# InterfacesB_FPGA.net
KiCad netlist of a schematic drawn in Altium Designer
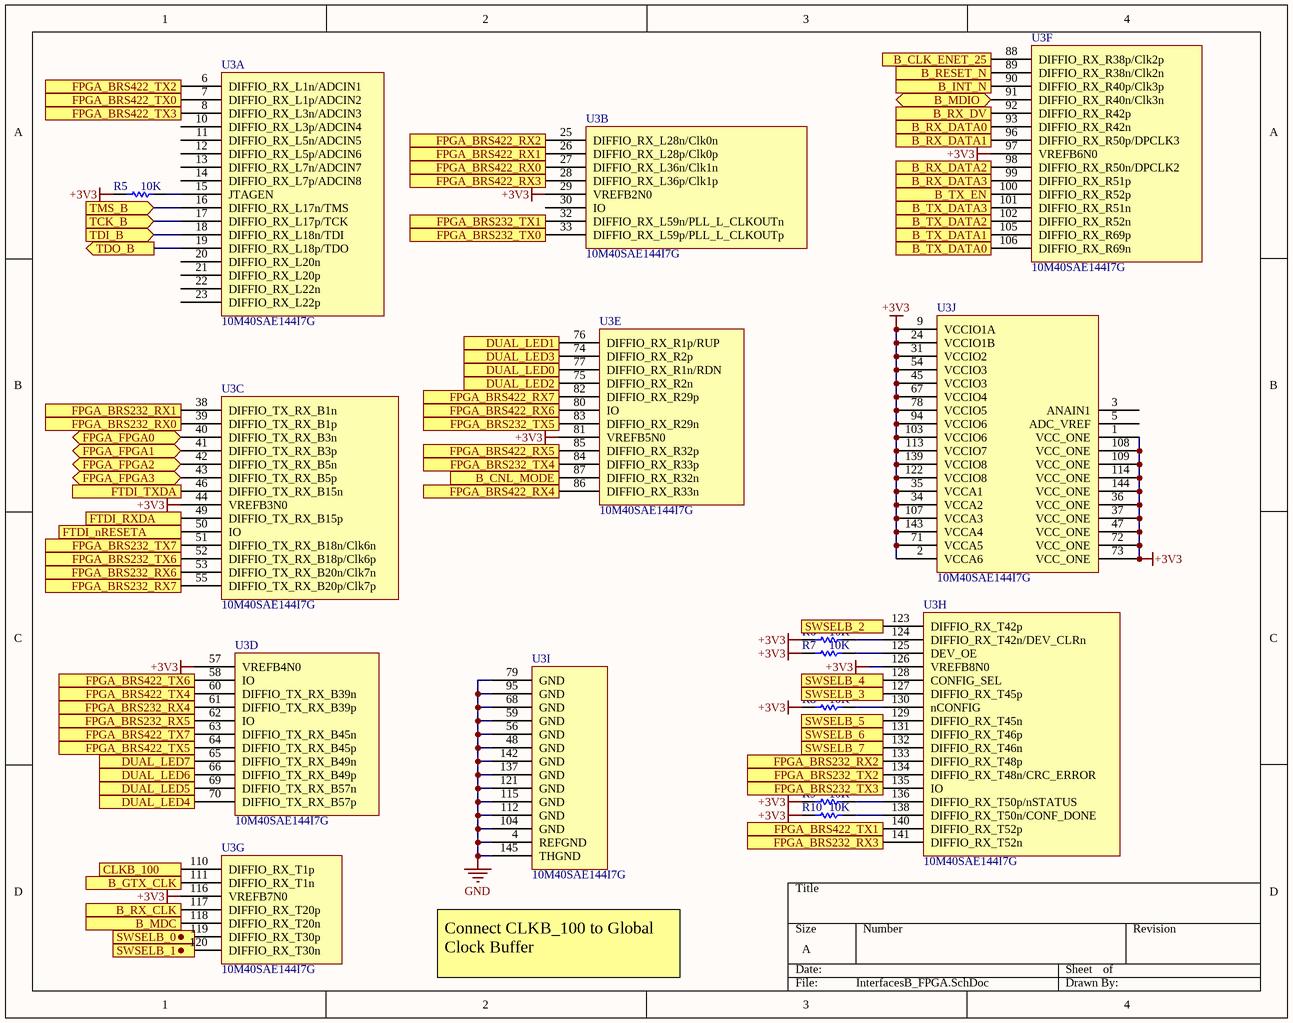
[diagram p0: InterfacesB_FPGA.SchDoc]

(export (version "E")
  (design (tool "Eeschema 10.0.6"))
  (components
    (comp (ref "R5")
      (value "10K")
      (footprint "RES_0805")
      (fields (field (name "Comment") "RES_0805"))
      (libsource (lib "AdapterLib") (part "RES_0805"))
    )
    (comp (ref "R6")
      (value "10K")
      (footprint "RES_0805")
      (fields (field (name "Comment") "RES_0805"))
      (libsource (lib "AdapterLib") (part "RES_0805"))
    )
    (comp (ref "R7")
      (value "10K")
      (footprint "RES_0805")
      (fields (field (name "Comment") "RES_0805"))
      (libsource (lib "AdapterLib") (part "RES_0805"))
    )
    (comp (ref "R8")
      (value "10K")
      (footprint "RES_0805")
      (fields (field (name "Comment") "RES_0805"))
      (libsource (lib "AdapterLib") (part "RES_0805"))
    )
    (comp (ref "R9")
      (value "10K")
      (footprint "RES_0805")
      (fields (field (name "Comment") "RES_0805"))
      (libsource (lib "AdapterLib") (part "RES_0805"))
    )
    (comp (ref "R10")
      (value "10K")
      (footprint "RES_0805")
      (fields (field (name "Comment") "RES_0805"))
      (libsource (lib "AdapterLib") (part "RES_0805"))
    )
    (comp (ref "U3")
      (value "10M40SAE144I7G")
      (footprint "10M40SAE144I7G")
      (description "IC FPGA 101 I/O 144EQFP")
      (libsource (lib "AdapterLib") (part "10M40SAE144I7G"))
    )
  )
  (nets
    (net (code "1") (name "+3V3") (class "Default")
      (node (ref "R10") (pin "2") (pinfunction "2_2") (pintype "passive"))
      (node (ref "R5") (pin "2") (pinfunction "2_2") (pintype "passive"))
      (node (ref "R6") (pin "2") (pinfunction "2_2") (pintype "passive"))
      (node (ref "R7") (pin "2") (pinfunction "2_2") (pintype "passive"))
      (node (ref "R8") (pin "2") (pinfunction "2_2") (pintype "passive"))
      (node (ref "R9") (pin "2") (pinfunction "2_2") (pintype "passive"))
      (node (ref "U3") (pin "1") (pinfunction "VCC_ONE_1") (pintype "passive"))
      (node (ref "U3") (pin "103") (pinfunction "VCCIO6_103") (pintype "passive"))
      (node (ref "U3") (pin "107") (pinfunction "VCCA3_107") (pintype "passive"))
      (node (ref "U3") (pin "108") (pinfunction "VCC_ONE_108") (pintype "passive"))
      (node (ref "U3") (pin "109") (pinfunction "VCC_ONE_109") (pintype "passive"))
      (node (ref "U3") (pin "113") (pinfunction "VCCIO7_113") (pintype "passive"))
      (node (ref "U3") (pin "114") (pinfunction "VCC_ONE_114") (pintype "passive"))
      (node (ref "U3") (pin "116") (pinfunction "VREFB7N0_116") (pintype "passive"))
      (node (ref "U3") (pin "122") (pinfunction "VCCIO8_122") (pintype "passive"))
      (node (ref "U3") (pin "126") (pinfunction "VREFB8N0_126") (pintype "passive"))
      (node (ref "U3") (pin "139") (pinfunction "VCCIO8_139") (pintype "passive"))
      (node (ref "U3") (pin "143") (pinfunction "VCCA4_143") (pintype "passive"))
      (node (ref "U3") (pin "144") (pinfunction "VCC_ONE_144") (pintype "passive"))
      (node (ref "U3") (pin "2") (pinfunction "VCCA6_2") (pintype "passive"))
      (node (ref "U3") (pin "24") (pinfunction "VCCIO1B_24") (pintype "passive"))
      (node (ref "U3") (pin "29") (pinfunction "VREFB2N0_29") (pintype "passive"))
      (node (ref "U3") (pin "31") (pinfunction "VCCIO2_31") (pintype "passive"))
      (node (ref "U3") (pin "34") (pinfunction "VCCA2_34") (pintype "passive"))
      (node (ref "U3") (pin "35") (pinfunction "VCCA1_35") (pintype "passive"))
      (node (ref "U3") (pin "36") (pinfunction "VCC_ONE_36") (pintype "passive"))
      (node (ref "U3") (pin "37") (pinfunction "VCC_ONE_37") (pintype "passive"))
      (node (ref "U3") (pin "44") (pinfunction "VREFB3N0_44") (pintype "passive"))
      (node (ref "U3") (pin "45") (pinfunction "VCCIO3_45") (pintype "passive"))
      (node (ref "U3") (pin "47") (pinfunction "VCC_ONE_47") (pintype "passive"))
      (node (ref "U3") (pin "54") (pinfunction "VCCIO3_54") (pintype "passive"))
      (node (ref "U3") (pin "57") (pinfunction "VREFB4N0_57") (pintype "passive"))
      (node (ref "U3") (pin "67") (pinfunction "VCCIO4_67") (pintype "passive"))
      (node (ref "U3") (pin "71") (pinfunction "VCCA5_71") (pintype "passive"))
      (node (ref "U3") (pin "72") (pinfunction "VCC_ONE_72") (pintype "passive"))
      (node (ref "U3") (pin "73") (pinfunction "VCC_ONE_73") (pintype "passive"))
      (node (ref "U3") (pin "78") (pinfunction "VCCIO5_78") (pintype "passive"))
      (node (ref "U3") (pin "81") (pinfunction "VREFB5N0_81") (pintype "passive"))
      (node (ref "U3") (pin "9") (pinfunction "VCCIO1A_9") (pintype "passive"))
      (node (ref "U3") (pin "94") (pinfunction "VCCIO6_94") (pintype "passive"))
      (node (ref "U3") (pin "97") (pinfunction "VREFB6N0_97") (pintype "passive"))
    )
    (net (code "2") (name "/B_CLK_ENET_25") (class "Default")
      (node (ref "U3") (pin "88") (pinfunction "DIFFIO_RX_R38p/Clk2p_88") (pintype "passive"))
    )
    (net (code "3") (name "/B_CNL_MODE") (class "Default")
      (node (ref "U3") (pin "87") (pinfunction "DIFFIO_RX_R32n_87") (pintype "passive"))
    )
    (net (code "4") (name "/B_GTX_CLK") (class "Default")
      (node (ref "U3") (pin "111") (pinfunction "DIFFIO_RX_T1n_111") (pintype "passive"))
    )
    (net (code "5") (name "/B_INT_N") (class "Default")
      (node (ref "U3") (pin "90") (pinfunction "DIFFIO_RX_R40p/Clk3p_90") (pintype "passive"))
    )
    (net (code "6") (name "/B_MDC") (class "Default")
      (node (ref "U3") (pin "118") (pinfunction "DIFFIO_RX_T20n_118") (pintype "passive"))
    )
    (net (code "7") (name "/B_MDIO") (class "Default")
      (node (ref "U3") (pin "91") (pinfunction "DIFFIO_RX_R40n/Clk3n_91") (pintype "passive"))
    )
    (net (code "8") (name "/B_RESET_N") (class "Default")
      (node (ref "U3") (pin "89") (pinfunction "DIFFIO_RX_R38n/Clk2n_89") (pintype "passive"))
    )
    (net (code "9") (name "/B_RX_CLK") (class "Default")
      (node (ref "U3") (pin "117") (pinfunction "DIFFIO_RX_T20p_117") (pintype "passive"))
    )
    (net (code "10") (name "/B_RX_DATA0") (class "Default")
      (node (ref "U3") (pin "93") (pinfunction "DIFFIO_RX_R42n_93") (pintype "passive"))
    )
    (net (code "11") (name "/B_RX_DATA1") (class "Default")
      (node (ref "U3") (pin "96") (pinfunction "DIFFIO_RX_R50p/DPCLK3_96") (pintype "passive"))
    )
    (net (code "12") (name "/B_RX_DATA2") (class "Default")
      (node (ref "U3") (pin "98") (pinfunction "DIFFIO_RX_R50n/DPCLK2_98") (pintype "passive"))
    )
    (net (code "13") (name "/B_RX_DATA3") (class "Default")
      (node (ref "U3") (pin "99") (pinfunction "DIFFIO_RX_R51p_99") (pintype "passive"))
    )
    (net (code "14") (name "/B_RX_DV") (class "Default")
      (node (ref "U3") (pin "92") (pinfunction "DIFFIO_RX_R42p_92") (pintype "passive"))
    )
    (net (code "15") (name "/B_TX_DATA0") (class "Default")
      (node (ref "U3") (pin "106") (pinfunction "DIFFIO_RX_R69n_106") (pintype "passive"))
    )
    (net (code "16") (name "/B_TX_DATA1") (class "Default")
      (node (ref "U3") (pin "105") (pinfunction "DIFFIO_RX_R69p_105") (pintype "passive"))
    )
    (net (code "17") (name "/B_TX_DATA2") (class "Default")
      (node (ref "U3") (pin "102") (pinfunction "DIFFIO_RX_R52n_102") (pintype "passive"))
    )
    (net (code "18") (name "/B_TX_DATA3") (class "Default")
      (node (ref "U3") (pin "101") (pinfunction "DIFFIO_RX_R51n_101") (pintype "passive"))
    )
    (net (code "19") (name "/B_TX_EN") (class "Default")
      (node (ref "U3") (pin "100") (pinfunction "DIFFIO_RX_R52p_100") (pintype "passive"))
    )
    (net (code "20") (name "/CLKB_100") (class "Default")
      (node (ref "U3") (pin "110") (pinfunction "DIFFIO_RX_T1p_110") (pintype "passive"))
    )
    (net (code "21") (name "/DUAL_LED0") (class "Default")
      (node (ref "U3") (pin "77") (pinfunction "DIFFIO_RX_R1n/RDN_77") (pintype "passive"))
    )
    (net (code "22") (name "/DUAL_LED1") (class "Default")
      (node (ref "U3") (pin "76") (pinfunction "DIFFIO_RX_R1p/RUP_76") (pintype "passive"))
    )
    (net (code "23") (name "/DUAL_LED2") (class "Default")
      (node (ref "U3") (pin "75") (pinfunction "DIFFIO_RX_R2n_75") (pintype "passive"))
    )
    (net (code "24") (name "/DUAL_LED3") (class "Default")
      (node (ref "U3") (pin "74") (pinfunction "DIFFIO_RX_R2p_74") (pintype "passive"))
    )
    (net (code "25") (name "/DUAL_LED4") (class "Default")
      (node (ref "U3") (pin "70") (pinfunction "DIFFIO_TX_RX_B57p_70") (pintype "passive"))
    )
    (net (code "26") (name "/DUAL_LED5") (class "Default")
      (node (ref "U3") (pin "69") (pinfunction "DIFFIO_TX_RX_B57n_69") (pintype "passive"))
    )
    (net (code "27") (name "/DUAL_LED6") (class "Default")
      (node (ref "U3") (pin "66") (pinfunction "DIFFIO_TX_RX_B49p_66") (pintype "passive"))
    )
    (net (code "28") (name "/DUAL_LED7") (class "Default")
      (node (ref "U3") (pin "65") (pinfunction "DIFFIO_TX_RX_B49n_65") (pintype "passive"))
    )
    (net (code "29") (name "/FPGA_BRS232_RX0") (class "Default")
      (node (ref "U3") (pin "39") (pinfunction "DIFFIO_TX_RX_B1p_39") (pintype "passive"))
    )
    (net (code "30") (name "/FPGA_BRS232_RX1") (class "Default")
      (node (ref "U3") (pin "38") (pinfunction "DIFFIO_TX_RX_B1n_38") (pintype "passive"))
    )
    (net (code "31") (name "/FPGA_BRS232_RX2") (class "Default")
      (node (ref "U3") (pin "133") (pinfunction "DIFFIO_RX_T48p_133") (pintype "passive"))
    )
    (net (code "32") (name "/FPGA_BRS232_RX3") (class "Default")
      (node (ref "U3") (pin "141") (pinfunction "DIFFIO_RX_T52n_141") (pintype "passive"))
    )
    (net (code "33") (name "/FPGA_BRS232_RX4") (class "Default")
      (node (ref "U3") (pin "61") (pinfunction "DIFFIO_TX_RX_B39p_61") (pintype "passive"))
    )
    (net (code "34") (name "/FPGA_BRS232_RX5") (class "Default")
      (node (ref "U3") (pin "62") (pinfunction "IO_62") (pintype "passive"))
    )
    (net (code "35") (name "/FPGA_BRS232_RX6") (class "Default")
      (node (ref "U3") (pin "53") (pinfunction "DIFFIO_TX_RX_B20n/Clk7n_53") (pintype "passive"))
    )
    (net (code "36") (name "/FPGA_BRS232_RX7") (class "Default")
      (node (ref "U3") (pin "55") (pinfunction "DIFFIO_TX_RX_B20p/Clk7p_55") (pintype "passive"))
    )
    (net (code "37") (name "/FPGA_BRS232_TX0") (class "Default")
      (node (ref "U3") (pin "33") (pinfunction "DIFFIO_RX_L59p/PLL_L_CLKOUTp_33") (pintype "passive"))
    )
    (net (code "38") (name "/FPGA_BRS232_TX1") (class "Default")
      (node (ref "U3") (pin "32") (pinfunction "DIFFIO_RX_L59n/PLL_L_CLKOUTn_32") (pintype "passive"))
    )
    (net (code "39") (name "/FPGA_BRS232_TX2") (class "Default")
      (node (ref "U3") (pin "134") (pinfunction "DIFFIO_RX_T48n/CRC_ERROR_134") (pintype "passive"))
    )
    (net (code "40") (name "/FPGA_BRS232_TX3") (class "Default")
      (node (ref "U3") (pin "135") (pinfunction "IO_135") (pintype "passive"))
    )
    (net (code "41") (name "/FPGA_BRS232_TX4") (class "Default")
      (node (ref "U3") (pin "84") (pinfunction "DIFFIO_RX_R33p_84") (pintype "passive"))
    )
    (net (code "42") (name "/FPGA_BRS232_TX5") (class "Default")
      (node (ref "U3") (pin "83") (pinfunction "DIFFIO_RX_R29n_83") (pintype "passive"))
    )
    (net (code "43") (name "/FPGA_BRS232_TX6") (class "Default")
      (node (ref "U3") (pin "52") (pinfunction "DIFFIO_TX_RX_B18p/Clk6p_52") (pintype "passive"))
    )
    (net (code "44") (name "/FPGA_BRS232_TX7") (class "Default")
      (node (ref "U3") (pin "51") (pinfunction "DIFFIO_TX_RX_B18n/Clk6n_51") (pintype "passive"))
    )
    (net (code "45") (name "/FPGA_BRS422_RX0") (class "Default")
      (node (ref "U3") (pin "27") (pinfunction "DIFFIO_RX_L36n/Clk1n_27") (pintype "passive"))
    )
    (net (code "46") (name "/FPGA_BRS422_RX1") (class "Default")
      (node (ref "U3") (pin "26") (pinfunction "DIFFIO_RX_L28p/Clk0p_26") (pintype "passive"))
    )
    (net (code "47") (name "/FPGA_BRS422_RX2") (class "Default")
      (node (ref "U3") (pin "25") (pinfunction "DIFFIO_RX_L28n/Clk0n_25") (pintype "passive"))
    )
    (net (code "48") (name "/FPGA_BRS422_RX3") (class "Default")
      (node (ref "U3") (pin "28") (pinfunction "DIFFIO_RX_L36p/Clk1p_28") (pintype "passive"))
    )
    (net (code "49") (name "/FPGA_BRS422_RX4") (class "Default")
      (node (ref "U3") (pin "86") (pinfunction "DIFFIO_RX_R33n_86") (pintype "passive"))
    )
    (net (code "50") (name "/FPGA_BRS422_RX5") (class "Default")
      (node (ref "U3") (pin "85") (pinfunction "DIFFIO_RX_R32p_85") (pintype "passive"))
    )
    (net (code "51") (name "/FPGA_BRS422_RX6") (class "Default")
      (node (ref "U3") (pin "80") (pinfunction "IO_80") (pintype "passive"))
    )
    (net (code "52") (name "/FPGA_BRS422_RX7") (class "Default")
      (node (ref "U3") (pin "82") (pinfunction "DIFFIO_RX_R29p_82") (pintype "passive"))
    )
    (net (code "53") (name "/FPGA_BRS422_TX0") (class "Default")
      (node (ref "U3") (pin "7") (pinfunction "DIFFIO_RX_L1p/ADCIN2_7") (pintype "passive"))
    )
    (net (code "54") (name "/FPGA_BRS422_TX1") (class "Default")
      (node (ref "U3") (pin "140") (pinfunction "DIFFIO_RX_T52p_140") (pintype "passive"))
    )
    (net (code "55") (name "/FPGA_BRS422_TX2") (class "Default")
      (node (ref "U3") (pin "6") (pinfunction "DIFFIO_RX_L1n/ADCIN1_6") (pintype "passive"))
    )
    (net (code "56") (name "/FPGA_BRS422_TX3") (class "Default")
      (node (ref "U3") (pin "8") (pinfunction "DIFFIO_RX_L3n/ADCIN3_8") (pintype "passive"))
    )
    (net (code "57") (name "/FPGA_BRS422_TX4") (class "Default")
      (node (ref "U3") (pin "60") (pinfunction "DIFFIO_TX_RX_B39n_60") (pintype "passive"))
    )
    (net (code "58") (name "/FPGA_BRS422_TX5") (class "Default")
      (node (ref "U3") (pin "64") (pinfunction "DIFFIO_TX_RX_B45p_64") (pintype "passive"))
    )
    (net (code "59") (name "/FPGA_BRS422_TX6") (class "Default")
      (node (ref "U3") (pin "58") (pinfunction "IO_58") (pintype "passive"))
    )
    (net (code "60") (name "/FPGA_BRS422_TX7") (class "Default")
      (node (ref "U3") (pin "63") (pinfunction "DIFFIO_TX_RX_B45n_63") (pintype "passive"))
    )
    (net (code "61") (name "/FPGA_FPGA0") (class "Default")
      (node (ref "U3") (pin "40") (pinfunction "DIFFIO_TX_RX_B3n_40") (pintype "passive"))
    )
    (net (code "62") (name "/FPGA_FPGA1") (class "Default")
      (node (ref "U3") (pin "41") (pinfunction "DIFFIO_TX_RX_B3p_41") (pintype "passive"))
    )
    (net (code "63") (name "/FPGA_FPGA2") (class "Default")
      (node (ref "U3") (pin "42") (pinfunction "DIFFIO_TX_RX_B5n_42") (pintype "passive"))
    )
    (net (code "64") (name "/FPGA_FPGA3") (class "Default")
      (node (ref "U3") (pin "43") (pinfunction "DIFFIO_TX_RX_B5p_43") (pintype "passive"))
    )
    (net (code "65") (name "/FTDI_RXDA") (class "Default")
      (node (ref "U3") (pin "49") (pinfunction "DIFFIO_TX_RX_B15p_49") (pintype "passive"))
    )
    (net (code "66") (name "/FTDI_TXDA") (class "Default")
      (node (ref "U3") (pin "46") (pinfunction "DIFFIO_TX_RX_B15n_46") (pintype "passive"))
    )
    (net (code "67") (name "/FTDI_nRESETA") (class "Default")
      (node (ref "U3") (pin "50") (pinfunction "IO_50") (pintype "passive"))
    )
    (net (code "70") (name "/SWSELB_2") (class "Default")
      (node (ref "U3") (pin "123") (pinfunction "DIFFIO_RX_T42p_123") (pintype "passive"))
    )
    (net (code "71") (name "/SWSELB_3") (class "Default")
      (node (ref "U3") (pin "127") (pinfunction "DIFFIO_RX_T45p_127") (pintype "passive"))
    )
    (net (code "72") (name "/SWSELB_4") (class "Default")
      (node (ref "U3") (pin "128") (pinfunction "CONFIG_SEL_128") (pintype "passive"))
    )
    (net (code "73") (name "/SWSELB_5") (class "Default")
      (node (ref "U3") (pin "129") (pinfunction "DIFFIO_RX_T45n_129") (pintype "passive"))
    )
    (net (code "74") (name "/SWSELB_6") (class "Default")
      (node (ref "U3") (pin "131") (pinfunction "DIFFIO_RX_T46p_131") (pintype "passive"))
    )
    (net (code "75") (name "/SWSELB_7") (class "Default")
      (node (ref "U3") (pin "132") (pinfunction "DIFFIO_RX_T46n_132") (pintype "passive"))
    )
    (net (code "76") (name "/TCK_B") (class "Default")
      (node (ref "U3") (pin "17") (pinfunction "DIFFIO_RX_L17p/TCK_17") (pintype "passive"))
    )
    (net (code "77") (name "/TDI_B") (class "Default")
      (node (ref "U3") (pin "18") (pinfunction "DIFFIO_RX_L18n/TDI_18") (pintype "passive"))
    )
    (net (code "78") (name "/TDO_B") (class "Default")
      (node (ref "U3") (pin "19") (pinfunction "DIFFIO_RX_L18p/TDO_19") (pintype "passive"))
    )
    (net (code "79") (name "/TMS_B") (class "Default")
      (node (ref "U3") (pin "16") (pinfunction "DIFFIO_RX_L17n/TMS_16") (pintype "passive"))
    )
    (net (code "80") (name "GND") (class "Default")
      (node (ref "U3") (pin "104") (pinfunction "GND_104") (pintype "passive"))
      (node (ref "U3") (pin "112") (pinfunction "GND_112") (pintype "passive"))
      (node (ref "U3") (pin "115") (pinfunction "GND_115") (pintype "passive"))
      (node (ref "U3") (pin "121") (pinfunction "GND_121") (pintype "passive"))
      (node (ref "U3") (pin "137") (pinfunction "GND_137") (pintype "passive"))
      (node (ref "U3") (pin "142") (pinfunction "GND_142") (pintype "passive"))
      (node (ref "U3") (pin "145") (pinfunction "THGND_145") (pintype "passive"))
      (node (ref "U3") (pin "4") (pinfunction "REFGND_4") (pintype "passive"))
      (node (ref "U3") (pin "48") (pinfunction "GND_48") (pintype "passive"))
      (node (ref "U3") (pin "56") (pinfunction "GND_56") (pintype "passive"))
      (node (ref "U3") (pin "59") (pinfunction "GND_59") (pintype "passive"))
      (node (ref "U3") (pin "68") (pinfunction "GND_68") (pintype "passive"))
      (node (ref "U3") (pin "79") (pinfunction "GND_79") (pintype "passive"))
      (node (ref "U3") (pin "95") (pinfunction "GND_95") (pintype "passive"))
    )
    (net (code "81") (name "Net-(U3A-JTAGEN)") (class "Default")
      (node (ref "R5") (pin "1") (pinfunction "1_1") (pintype "passive"))
      (node (ref "U3") (pin "15") (pinfunction "JTAGEN_15") (pintype "passive"))
    )
    (net (code "82") (name "Net-(U3H-DEV_OE)") (class "Default")
      (node (ref "R7") (pin "1") (pinfunction "1_1") (pintype "passive"))
      (node (ref "U3") (pin "125") (pinfunction "DEV_OE_125") (pintype "passive"))
    )
    (net (code "83") (name "Net-(U3H-DIFFIO_RX_T42n{slash}DEV_CLRn)") (class "Default")
      (node (ref "R6") (pin "1") (pinfunction "1_1") (pintype "passive"))
      (node (ref "U3") (pin "124") (pinfunction "DIFFIO_RX_T42n/DEV_CLRn_124") (pintype "passive"))
    )
    (net (code "84") (name "Net-(U3H-DIFFIO_RX_T50n{slash}CONF_DONE)") (class "Default")
      (node (ref "R10") (pin "1") (pinfunction "1_1") (pintype "passive"))
      (node (ref "U3") (pin "138") (pinfunction "DIFFIO_RX_T50n/CONF_DONE_138") (pintype "passive"))
    )
    (net (code "85") (name "Net-(U3H-DIFFIO_RX_T50p{slash}nSTATUS)") (class "Default")
      (node (ref "R9") (pin "1") (pinfunction "1_1") (pintype "passive"))
      (node (ref "U3") (pin "136") (pinfunction "DIFFIO_RX_T50p/nSTATUS_136") (pintype "passive"))
    )
    (net (code "86") (name "Net-(U3H-nCONFIG)") (class "Default")
      (node (ref "R8") (pin "1") (pinfunction "1_1") (pintype "passive"))
      (node (ref "U3") (pin "130") (pinfunction "nCONFIG_130") (pintype "passive"))
    )
    (net (code "87") (name "unconnected-(U3A-DIFFIO_RX_L3p{slash}ADCIN4-Pad10)") (class "Default")
      (node (ref "U3") (pin "10") (pinfunction "DIFFIO_RX_L3p/ADCIN4_10") (pintype "passive"))
    )
    (net (code "88") (name "unconnected-(U3A-DIFFIO_RX_L5n{slash}ADCIN5-Pad11)") (class "Default")
      (node (ref "U3") (pin "11") (pinfunction "DIFFIO_RX_L5n/ADCIN5_11") (pintype "passive"))
    )
    (net (code "89") (name "unconnected-(U3A-DIFFIO_RX_L5p{slash}ADCIN6-Pad12)") (class "Default")
      (node (ref "U3") (pin "12") (pinfunction "DIFFIO_RX_L5p/ADCIN6_12") (pintype "passive"))
    )
    (net (code "90") (name "unconnected-(U3A-DIFFIO_RX_L7n{slash}ADCIN7-Pad13)") (class "Default")
      (node (ref "U3") (pin "13") (pinfunction "DIFFIO_RX_L7n/ADCIN7_13") (pintype "passive"))
    )
    (net (code "91") (name "unconnected-(U3A-DIFFIO_RX_L7p{slash}ADCIN8-Pad14)") (class "Default")
      (node (ref "U3") (pin "14") (pinfunction "DIFFIO_RX_L7p/ADCIN8_14") (pintype "passive"))
    )
    (net (code "92") (name "unconnected-(U3A-DIFFIO_RX_L20n-Pad20)") (class "Default")
      (node (ref "U3") (pin "20") (pinfunction "DIFFIO_RX_L20n_20") (pintype "passive"))
    )
    (net (code "93") (name "unconnected-(U3A-DIFFIO_RX_L20p-Pad21)") (class "Default")
      (node (ref "U3") (pin "21") (pinfunction "DIFFIO_RX_L20p_21") (pintype "passive"))
    )
    (net (code "94") (name "unconnected-(U3A-DIFFIO_RX_L22n-Pad22)") (class "Default")
      (node (ref "U3") (pin "22") (pinfunction "DIFFIO_RX_L22n_22") (pintype "passive"))
    )
    (net (code "95") (name "unconnected-(U3A-DIFFIO_RX_L22p-Pad23)") (class "Default")
      (node (ref "U3") (pin "23") (pinfunction "DIFFIO_RX_L22p_23") (pintype "passive"))
    )
    (net (code "96") (name "unconnected-(U3B-IO-Pad30)") (class "Default")
      (node (ref "U3") (pin "30") (pinfunction "IO_30") (pintype "passive"))
    )
    (net (code "97") (name "unconnected-(U3G-DIFFIO_RX_T30n-Pad120)") (class "Default")
      (node (ref "U3") (pin "120") (pinfunction "DIFFIO_RX_T30n_120") (pintype "passive"))
    )
    (net (code "98") (name "unconnected-(U3G-DIFFIO_RX_T30p-Pad119)") (class "Default")
      (node (ref "U3") (pin "119") (pinfunction "DIFFIO_RX_T30p_119") (pintype "passive"))
    )
    (net (code "99") (name "unconnected-(U3J-ADC_VREF-Pad5)") (class "Default")
      (node (ref "U3") (pin "5") (pinfunction "ADC_VREF_5") (pintype "passive"))
    )
    (net (code "100") (name "unconnected-(U3J-ANAIN1-Pad3)") (class "Default")
      (node (ref "U3") (pin "3") (pinfunction "ANAIN1_3") (pintype "passive"))
    )
  )
)
